# 6__PSU.net
KiCad netlist of a schematic drawn in Altium Designer
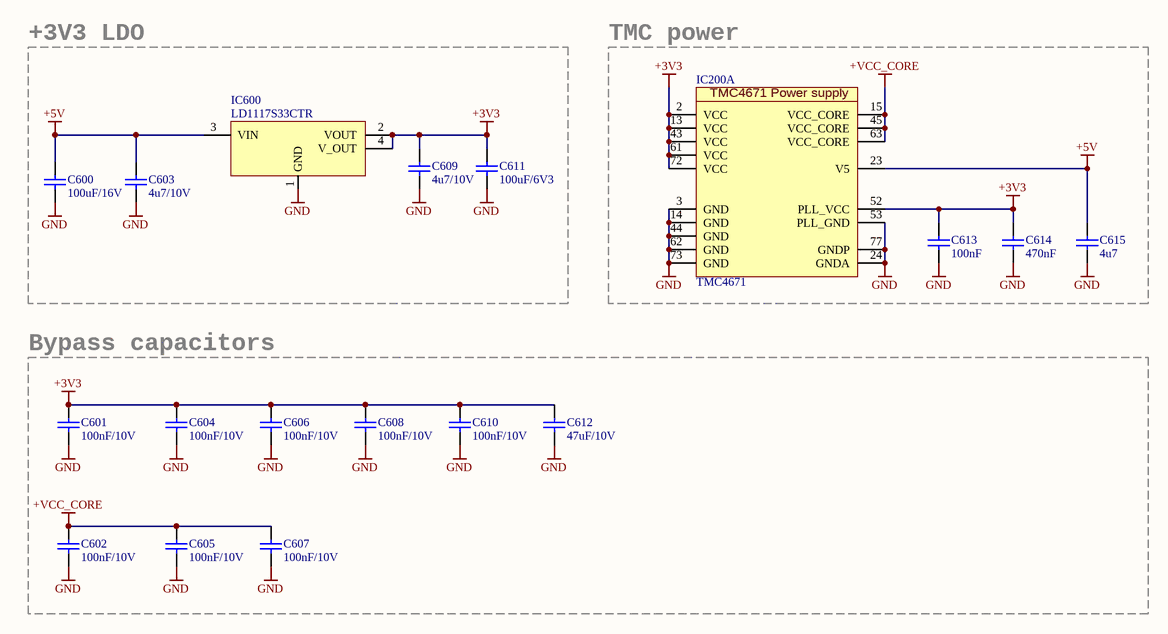
[diagram p0: [6]_PSU.SchDoc]

(export (version "E")
  (design (tool "Eeschema 10.0.6"))
  (components
    (comp (ref "C600")
      (value "100uF/16V")
      (footprint "C1210")
      (description "SMD Multilayer Ceramic Capacitor, 1210 [3225 Metric], 100 µF, 16 V, ± 20%, X5R, M Series")
      (fields (field (name "MF") "TAIYO YUDEN") (field (name "MPN") "EMK325ABJ107MM-T"))
      (libsource (lib "SMD_Passives") (part "C, 100 µF, 16 V, ± 20%, X5R, M Series, 1210"))
    )
    (comp (ref "C601")
      (value "100nF/10V")
      (footprint "C0603")
      (description "SMD Multilayer Ceramic Capacitor, 0603 [1608 Metric], 0.1 µF, 10 V, ± 10%, X7R, MC Series")
      (fields (field (name "MF") "Multicomp") (field (name "MPN") "MC0603B104K100CT"))
      (libsource (lib "SMD_Passives") (part "C, 0.1 µF, 10 V, ± 10%, X7R, 0603"))
    )
    (comp (ref "C602")
      (value "100nF/10V")
      (footprint "C0603")
      (description "SMD Multilayer Ceramic Capacitor, 0603 [1608 Metric], 0.1 µF, 10 V, ± 10%, X7R, MC Series")
      (fields (field (name "MF") "Multicomp") (field (name "MPN") "MC0603B104K100CT"))
      (libsource (lib "SMD_Passives") (part "C, 0.1 µF, 10 V, ± 10%, X7R, 0603"))
    )
    (comp (ref "C603")
      (value "4u7/10V")
      (footprint "C0603")
      (description "SMD Multilayer Ceramic Capacitor, 0603 [1608 Metric], 4.7 µF, 10 V, ± 10%, X5R, MC Series")
      (fields (field (name "MF") "MULTICOMP") (field (name "MPN") "MC0603X475K100CT"))
      (libsource (lib "SMD_Passives") (part "C, 4.7 µF, 10 V, ± 10%, X5R, MC Series , 0603"))
    )
    (comp (ref "C604")
      (value "100nF/10V")
      (footprint "C0603")
      (description "SMD Multilayer Ceramic Capacitor, 0603 [1608 Metric], 0.1 µF, 10 V, ± 10%, X7R, MC Series")
      (fields (field (name "MF") "Multicomp") (field (name "MPN") "MC0603B104K100CT"))
      (libsource (lib "SMD_Passives") (part "C, 0.1 µF, 10 V, ± 10%, X7R, 0603"))
    )
    (comp (ref "C605")
      (value "100nF/10V")
      (footprint "C0603")
      (description "SMD Multilayer Ceramic Capacitor, 0603 [1608 Metric], 0.1 µF, 10 V, ± 10%, X7R, MC Series")
      (fields (field (name "MF") "Multicomp") (field (name "MPN") "MC0603B104K100CT"))
      (libsource (lib "SMD_Passives") (part "C, 0.1 µF, 10 V, ± 10%, X7R, 0603"))
    )
    (comp (ref "C606")
      (value "100nF/10V")
      (footprint "C0603")
      (description "SMD Multilayer Ceramic Capacitor, 0603 [1608 Metric], 0.1 µF, 10 V, ± 10%, X7R, MC Series")
      (fields (field (name "MF") "Multicomp") (field (name "MPN") "MC0603B104K100CT"))
      (libsource (lib "SMD_Passives") (part "C, 0.1 µF, 10 V, ± 10%, X7R, 0603"))
    )
    (comp (ref "C607")
      (value "100nF/10V")
      (footprint "C0603")
      (description "SMD Multilayer Ceramic Capacitor, 0603 [1608 Metric], 0.1 µF, 10 V, ± 10%, X7R, MC Series")
      (fields (field (name "MF") "Multicomp") (field (name "MPN") "MC0603B104K100CT"))
      (libsource (lib "SMD_Passives") (part "C, 0.1 µF, 10 V, ± 10%, X7R, 0603"))
    )
    (comp (ref "C608")
      (value "100nF/10V")
      (footprint "C0603")
      (description "SMD Multilayer Ceramic Capacitor, 0603 [1608 Metric], 0.1 µF, 10 V, ± 10%, X7R, MC Series")
      (fields (field (name "MF") "Multicomp") (field (name "MPN") "MC0603B104K100CT"))
      (libsource (lib "SMD_Passives") (part "C, 0.1 µF, 10 V, ± 10%, X7R, 0603"))
    )
    (comp (ref "C609")
      (value "4u7/10V")
      (footprint "C0603")
      (description "SMD Multilayer Ceramic Capacitor, 0603 [1608 Metric], 4.7 µF, 10 V, ± 10%, X5R, MC Series")
      (fields (field (name "MF") "MULTICOMP") (field (name "MPN") "MC0603X475K100CT"))
      (libsource (lib "SMD_Passives") (part "C, 4.7 µF, 10 V, ± 10%, X5R, MC Series , 0603"))
    )
    (comp (ref "C610")
      (value "100nF/10V")
      (footprint "C0603")
      (description "SMD Multilayer Ceramic Capacitor, 0603 [1608 Metric], 0.1 µF, 10 V, ± 10%, X7R, MC Series")
      (fields (field (name "MF") "Multicomp") (field (name "MPN") "MC0603B104K100CT"))
      (libsource (lib "SMD_Passives") (part "C, 0.1 µF, 10 V, ± 10%, X7R, 0603"))
    )
    (comp (ref "C611")
      (value "100uF/6V3")
      (footprint "C1210")
      (description "SMD Multilayer Ceramic Capacitor, 1210 [3225 Metric], 100 µF, 6.3 V, ± 20%, X5R, GRM Series")
      (fields (field (name "MF") "MURATA") (field (name "MPN") "GRM31CR60J107ME39L."))
      (libsource (lib "SMD_Passives") (part "C, 100 µF, 6.3 V, ± 20%, X5R, GRM Series, 1210"))
    )
    (comp (ref "C612")
      (value "47uF/10V")
      (footprint "C1206")
      (description "SMD Multilayer Ceramic Capacitor, 1206 [3216 Metric], 47 µF, 10 V, ± 20%, X5R, GRM Series")
      (fields (field (name "MF") "MURATA") (field (name "MPN") "GRM31CR61A476ME15L"))
      (libsource (lib "SMD_Passives") (part "C, 47 µF, 10 V, ± 20%, X7R, MC Series , 1206"))
    )
    (comp (ref "C613")
      (value "100nF")
      (footprint "C0603")
      (description "SMD Multilayer Ceramic Capacitor, 0603 [1608 Metric], 0.1 µF, 10 V, ± 10%, X7R, MC Series")
      (fields (field (name "MF") "Multicomp") (field (name "MPN") "MC0603B104K100CT"))
      (libsource (lib "SMD_Passives") (part "C, 0.1 µF, 10 V, ± 10%, X7R, 0603"))
    )
    (comp (ref "C614")
      (value "470nF")
      (footprint "C0603")
      (description "SMD Multilayer Ceramic Capacitor, 0603 [1608 Metric], 0.47 µF, 16 V, ± 10%, X5R, MC Series")
      (fields (field (name "MF") "Multicomp") (field (name "MPN") "MC0603X474K160CT"))
      (libsource (lib "SMD_Passives") (part "C, 0.47 µF, 16 V, ± 10%, X5R, MC Series, 0603 [1608 Metric]"))
    )
    (comp (ref "C615")
      (value "4u7")
      (footprint "C0603")
      (description "SMD Multilayer Ceramic Capacitor, 0603 [1608 Metric], 4.7 µF, 10 V, ± 10%, X5R, MC Series")
      (fields (field (name "MF") "MULTICOMP") (field (name "MPN") "MC0603X475K100CT"))
      (libsource (lib "SMD_Passives") (part "C, 4.7 µF, 10 V, ± 10%, X5R, MC Series , 0603"))
    )
    (comp (ref "IC200")
      (value "TMC4671")
      (footprint "QFN40P1050X650X90_HS-77N")
      (fields (field (name "MF") "TRINAMIC"))
      (libsource (lib "TMC4671-EVAL_V1_0") (part "TMC4671"))
    )
    (comp (ref "IC600")
      (value "LD1117S33CTR")
      (footprint "SOT230P700X180-4N")
      (description "Fixed LDO Voltage Regulator, 4.75V to 15V, 1.1V Dropout, 3.3Vout, 950mAout, SOT-223-4")
      (fields (field (name "MF") "STMICROELECTRONICS"))
      (libsource (lib "TMC4671-EVAL_V1_0") (part "LDO_LD1117S33CTR"))
    )
  )
  (nets
    (net (code "1") (name "+3V3") (class "Default")
      (node (ref "C601") (pin "2") (pinfunction "2_2") (pintype "passive"))
      (node (ref "C604") (pin "2") (pinfunction "2_2") (pintype "passive"))
      (node (ref "C606") (pin "2") (pinfunction "2_2") (pintype "passive"))
      (node (ref "C608") (pin "2") (pinfunction "2_2") (pintype "passive"))
      (node (ref "C609") (pin "2") (pinfunction "2_2") (pintype "passive"))
      (node (ref "C610") (pin "2") (pinfunction "2_2") (pintype "passive"))
      (node (ref "C611") (pin "2") (pinfunction "2_2") (pintype "passive"))
      (node (ref "C612") (pin "2") (pinfunction "2_2") (pintype "passive"))
      (node (ref "C613") (pin "2") (pinfunction "2_2") (pintype "passive"))
      (node (ref "C614") (pin "1") (pinfunction "1_1") (pintype "passive"))
      (node (ref "IC200") (pin "13") (pinfunction "VCC_13") (pintype "power_in"))
      (node (ref "IC200") (pin "2") (pinfunction "VCC_2") (pintype "power_in"))
      (node (ref "IC200") (pin "43") (pinfunction "VCC_43") (pintype "power_in"))
      (node (ref "IC200") (pin "52") (pinfunction "PLL_VCC_52") (pintype "power_in"))
      (node (ref "IC200") (pin "61") (pinfunction "VCC_61") (pintype "power_in"))
      (node (ref "IC200") (pin "72") (pinfunction "VCC_72") (pintype "power_in"))
      (node (ref "IC600") (pin "2") (pinfunction "VOUT_2") (pintype "passive"))
      (node (ref "IC600") (pin "4") (pinfunction "V_OUT_4") (pintype "passive"))
    )
    (net (code "2") (name "+5V") (class "Default")
      (node (ref "C600") (pin "2") (pinfunction "2_2") (pintype "passive"))
      (node (ref "C603") (pin "2") (pinfunction "2_2") (pintype "passive"))
      (node (ref "C615") (pin "2") (pinfunction "2_2") (pintype "passive"))
      (node (ref "IC200") (pin "23") (pinfunction "V5_23") (pintype "power_in"))
      (node (ref "IC600") (pin "3") (pinfunction "VIN_3") (pintype "passive"))
    )
    (net (code "3") (name "+VCC_CORE") (class "Default")
      (node (ref "C602") (pin "2") (pinfunction "2_2") (pintype "passive"))
      (node (ref "C605") (pin "2") (pinfunction "2_2") (pintype "passive"))
      (node (ref "C607") (pin "2") (pinfunction "2_2") (pintype "passive"))
      (node (ref "IC200") (pin "15") (pinfunction "VCC_CORE_15") (pintype "power_in"))
      (node (ref "IC200") (pin "45") (pinfunction "VCC_CORE_45") (pintype "power_in"))
      (node (ref "IC200") (pin "63") (pinfunction "VCC_CORE_63") (pintype "power_in"))
    )
    (net (code "4") (name "GND") (class "Default")
      (node (ref "C600") (pin "1") (pinfunction "1_1") (pintype "passive"))
      (node (ref "C601") (pin "1") (pinfunction "1_1") (pintype "passive"))
      (node (ref "C602") (pin "1") (pinfunction "1_1") (pintype "passive"))
      (node (ref "C603") (pin "1") (pinfunction "1_1") (pintype "passive"))
      (node (ref "C604") (pin "1") (pinfunction "1_1") (pintype "passive"))
      (node (ref "C605") (pin "1") (pinfunction "1_1") (pintype "passive"))
      (node (ref "C606") (pin "1") (pinfunction "1_1") (pintype "passive"))
      (node (ref "C607") (pin "1") (pinfunction "1_1") (pintype "passive"))
      (node (ref "C608") (pin "1") (pinfunction "1_1") (pintype "passive"))
      (node (ref "C609") (pin "1") (pinfunction "1_1") (pintype "passive"))
      (node (ref "C610") (pin "1") (pinfunction "1_1") (pintype "passive"))
      (node (ref "C611") (pin "1") (pinfunction "1_1") (pintype "passive"))
      (node (ref "C612") (pin "1") (pinfunction "1_1") (pintype "passive"))
      (node (ref "C613") (pin "1") (pinfunction "1_1") (pintype "passive"))
      (node (ref "C614") (pin "2") (pinfunction "2_2") (pintype "passive"))
      (node (ref "C615") (pin "1") (pinfunction "1_1") (pintype "passive"))
      (node (ref "IC200") (pin "14") (pinfunction "GND_14") (pintype "power_in"))
      (node (ref "IC200") (pin "24") (pinfunction "GNDA_24") (pintype "power_in"))
      (node (ref "IC200") (pin "3") (pinfunction "GND_3") (pintype "power_in"))
      (node (ref "IC200") (pin "44") (pinfunction "GND_44") (pintype "power_in"))
      (node (ref "IC200") (pin "53") (pinfunction "PLL_GND_53") (pintype "power_in"))
      (node (ref "IC200") (pin "62") (pinfunction "GND_62") (pintype "power_in"))
      (node (ref "IC200") (pin "73") (pinfunction "GND_73") (pintype "power_in"))
      (node (ref "IC200") (pin "77") (pinfunction "GNDP_77") (pintype "power_in"))
      (node (ref "IC600") (pin "1") (pinfunction "GND_1") (pintype "passive"))
    )
  )
)
